# 4_Solder-Pen.net
KiCad netlist of a schematic drawn in Altium Designer
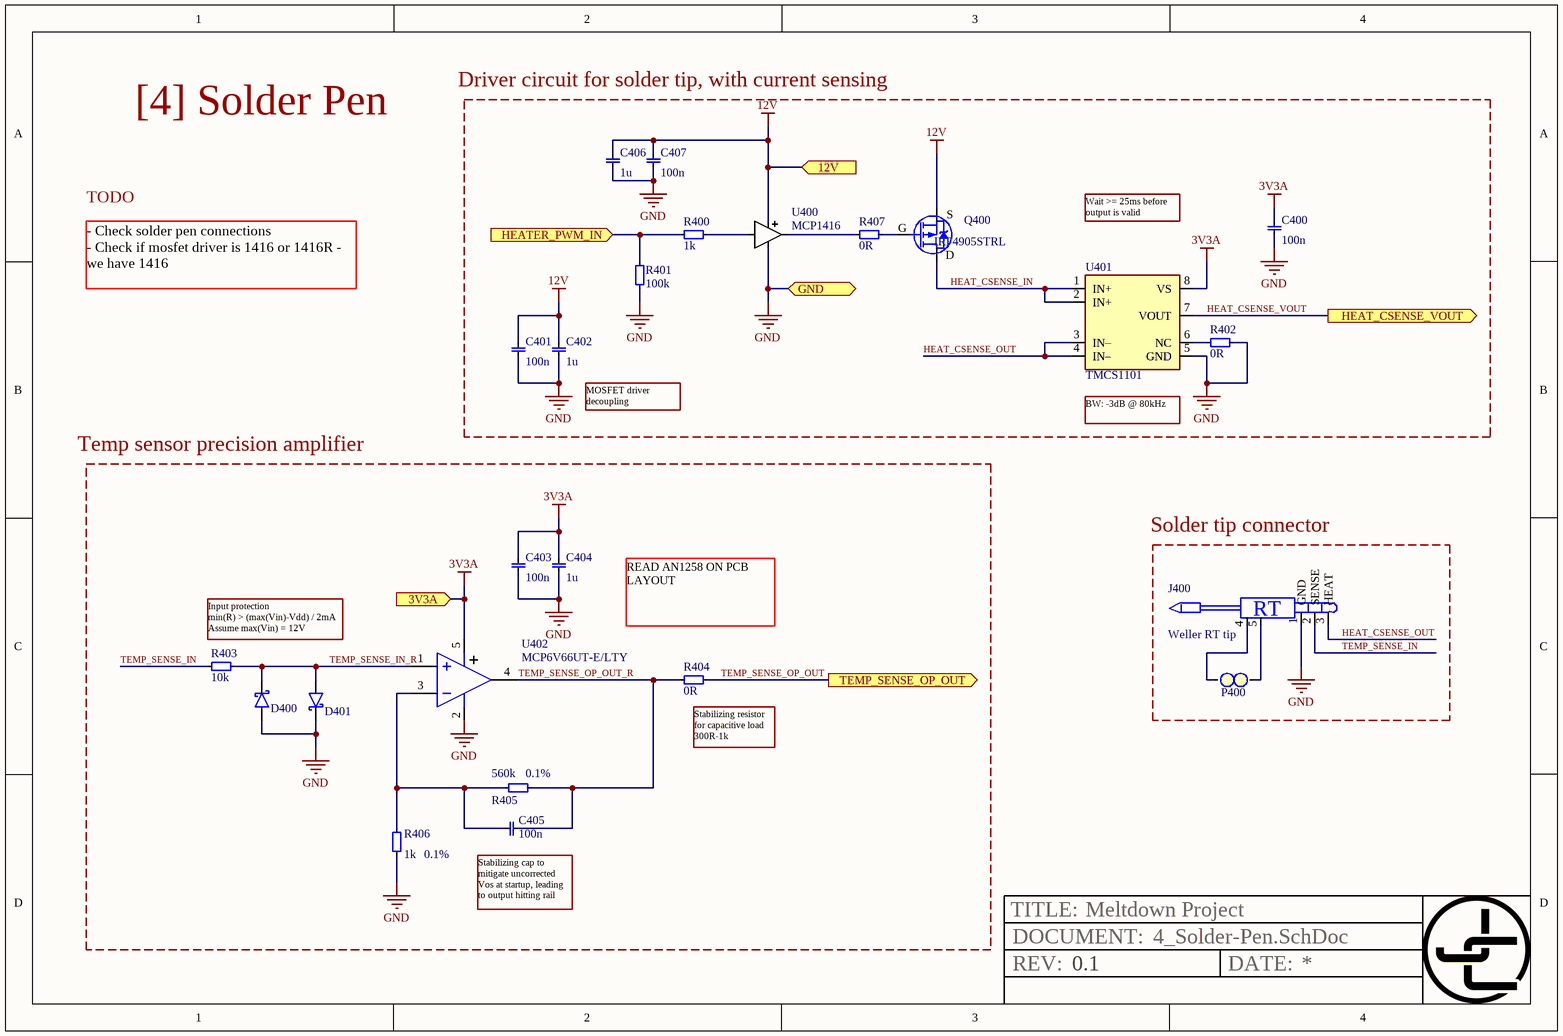
[diagram p0: 4_Solder-Pen.SchDoc]

(export (version "E")
  (design (tool "Eeschema 10.0.6"))
  (components
    (comp (ref "C400")
      (value "100n")
      (footprint "0805, cap")
      (fields (field (name "Comment") "0805, capacitor"))
      (libsource (lib "jclib") (part "0805, capacitor"))
    )
    (comp (ref "C401")
      (value "100n")
      (footprint "0805, cap")
      (fields (field (name "Comment") "0805, capacitor"))
      (libsource (lib "jclib") (part "0805, capacitor"))
    )
    (comp (ref "C402")
      (value "1u")
      (footprint "0805, cap")
      (fields (field (name "Comment") "0805, capacitor"))
      (libsource (lib "jclib") (part "0805, capacitor"))
    )
    (comp (ref "C403")
      (value "100n")
      (footprint "0805, cap")
      (fields (field (name "Comment") "0805, capacitor"))
      (libsource (lib "jclib") (part "0805, capacitor"))
    )
    (comp (ref "C404")
      (value "1u")
      (footprint "0805, cap")
      (fields (field (name "Comment") "0805, capacitor"))
      (libsource (lib "jclib") (part "0805, capacitor"))
    )
    (comp (ref "C405")
      (value "100n")
      (footprint "0805, cap")
      (fields (field (name "Comment") "0805, capacitor"))
      (libsource (lib "jclib") (part "0805, capacitor"))
    )
    (comp (ref "C406")
      (value "1u")
      (footprint "0805, cap")
      (fields (field (name "Comment") "0805, capacitor"))
      (libsource (lib "jclib") (part "0805, capacitor"))
    )
    (comp (ref "C407")
      (value "100n")
      (footprint "0805, cap")
      (fields (field (name "Comment") "0805, capacitor"))
      (libsource (lib "jclib") (part "0805, capacitor"))
    )
    (comp (ref "D400")
      (value "B340A")
      (footprint "DO-214AC")
      (description "SchottkydiodE, 40 V, 3 A")
      (libsource (lib "jclib") (part "B340A-E3/61T"))
    )
    (comp (ref "D401")
      (value "B340A")
      (footprint "DO-214AC")
      (description "SchottkydiodE, 40 V, 3 A")
      (libsource (lib "jclib") (part "B340A-E3/61T"))
    )
    (comp (ref "J400")
      (value "Weller RT tip")
      (footprint "5 POLE BLOCK CONNECTOR")
      (libsource (lib "jclib") (part "Weller RT tip"))
    )
    (comp (ref "P400")
      (value "1x2 Pin Heade Straight")
      (footprint "padtwo_L")
      (description "2.54 mm, TH")
      (libsource (lib "jclib") (part "1x2 Pin Heade Straight"))
    )
    (comp (ref "Q400")
      (value "IRF4905")
      (footprint "d2pak")
      (description "P-Channel HEXFET® Power MOSFET")
      (libsource (lib "jclib") (part "IRF4905"))
    )
    (comp (ref "R400")
      (value "1k")
      (footprint "0603")
      (fields (field (name "Comment") "0603, resistor"))
      (libsource (lib "jclib") (part "0603, resistor"))
    )
    (comp (ref "R401")
      (value "100k")
      (footprint "0603")
      (fields (field (name "Comment") "0603, resistor"))
      (libsource (lib "jclib") (part "0603, resistor"))
    )
    (comp (ref "R402")
      (value "0R")
      (footprint "0603")
      (fields (field (name "Comment") "0603, resistor"))
      (libsource (lib "jclib") (part "0603, resistor"))
    )
    (comp (ref "R403")
      (value "10k")
      (footprint "0603")
      (fields (field (name "Comment") "0603, resistor"))
      (libsource (lib "jclib") (part "0603, resistor"))
    )
    (comp (ref "R404")
      (value "0R")
      (footprint "0603")
      (fields (field (name "Comment") "0603, resistor"))
      (libsource (lib "jclib") (part "0603, resistor"))
    )
    (comp (ref "R405")
      (value "560k")
      (footprint "0603")
      (fields (field (name "TOLERANCE") "0.1%") (field (name "Comment") "0603, resistor"))
      (libsource (lib "jclib") (part "0603, resistor"))
    )
    (comp (ref "R406")
      (value "1k")
      (footprint "0603")
      (fields (field (name "TOLERANCE") "0.1%") (field (name "Comment") "0603, resistor"))
      (libsource (lib "jclib") (part "0603, resistor"))
    )
    (comp (ref "R407")
      (value "0R")
      (footprint "0603")
      (fields (field (name "Comment") "0603, resistor"))
      (libsource (lib "jclib") (part "0603, resistor"))
    )
    (comp (ref "U400")
      (value "MCP1416")
      (footprint "SOT23-5")
      (description "High-speed Power MOSFET driver")
      (libsource (lib "jclib") (part "MCP1416"))
    )
    (comp (ref "U401")
      (value "TMCS1101")
      (footprint "SOIC8")
      (description "Hall-Effect Current Sensor")
      (libsource (lib "jclib") (part "TMCS1101"))
    )
    (comp (ref "U402")
      (value "MCP6V66UT-E/LTY")
      (footprint "SC70P210X110-5N")
      (description "Linear High Precision Op Amps-Chopper Stabilized, 1000kHz, 1.8Vto5.5V, SC70-5, RoHS")
      (fields (field (name "MANUFACTURER") "Microchip"))
      (libsource (lib "jclib") (part "MCP6V66UT-E/LTY"))
    )
  )
  (nets
    (net (code "1") (name "/HEATER_PWM_IN") (class "Default")
      (node (ref "R400") (pin "1") (pinfunction "1_1") (pintype "passive"))
      (node (ref "R401") (pin "0") (pinfunction "0_0") (pintype "passive"))
    )
    (net (code "2") (name "/HEAT_CSENSE_IN") (class "Default")
      (node (ref "Q400") (pin "2") (pinfunction "D_2") (pintype "passive"))
      (node (ref "U401") (pin "1") (pinfunction "IN+_1") (pintype "passive"))
      (node (ref "U401") (pin "2") (pinfunction "IN+_2") (pintype "passive"))
    )
    (net (code "3") (name "/HEAT_CSENSE_OUT") (class "Default")
      (node (ref "J400") (pin "3") (pinfunction "HEAT_3") (pintype "passive"))
      (node (ref "U401") (pin "3") (pinfunction "IN–_3") (pintype "passive"))
      (node (ref "U401") (pin "4") (pinfunction "IN–_4") (pintype "passive"))
    )
    (net (code "4") (name "/HEAT_CSENSE_VOUT") (class "Default")
      (node (ref "U401") (pin "7") (pinfunction "VOUT_7") (pintype "passive"))
    )
    (net (code "5") (name "/TEMP_SENSE_IN") (class "Default")
      (node (ref "J400") (pin "2") (pinfunction "SENSE_2") (pintype "passive"))
      (node (ref "R403") (pin "0") (pinfunction "0_0") (pintype "passive"))
    )
    (net (code "6") (name "/TEMP_SENSE_IN_R") (class "Default")
      (node (ref "D400") (pin "1") (pinfunction "K_1") (pintype "passive"))
      (node (ref "D401") (pin "2") (pinfunction "A_2") (pintype "passive"))
      (node (ref "R403") (pin "1") (pinfunction "1_1") (pintype "passive"))
      (node (ref "U402") (pin "1") (pinfunction "IN+_1") (pintype "passive"))
    )
    (net (code "7") (name "/TEMP_SENSE_OP_OUT") (class "Default")
      (node (ref "R404") (pin "1") (pinfunction "1_1") (pintype "passive"))
    )
    (net (code "8") (name "/TEMP_SENSE_OP_OUT_R") (class "Default")
      (node (ref "C405") (pin "0") (pinfunction "0_0") (pintype "passive"))
      (node (ref "R404") (pin "0") (pinfunction "0_0") (pintype "passive"))
      (node (ref "R405") (pin "1") (pinfunction "1_1") (pintype "passive"))
      (node (ref "U402") (pin "4") (pinfunction "OUT_4") (pintype "passive"))
    )
    (net (code "9") (name "3V3A") (class "Default")
      (node (ref "C400") (pin "1") (pinfunction "1_1") (pintype "passive"))
      (node (ref "C403") (pin "1") (pinfunction "1_1") (pintype "passive"))
      (node (ref "C404") (pin "1") (pinfunction "1_1") (pintype "passive"))
      (node (ref "U401") (pin "8") (pinfunction "VS_8") (pintype "passive"))
      (node (ref "U402") (pin "5") (pinfunction "V+_5") (pintype "passive"))
    )
    (net (code "10") (name "12V") (class "Default")
      (node (ref "C401") (pin "1") (pinfunction "1_1") (pintype "passive"))
      (node (ref "C402") (pin "1") (pinfunction "1_1") (pintype "passive"))
      (node (ref "C406") (pin "1") (pinfunction "1_1") (pintype "passive"))
      (node (ref "C407") (pin "1") (pinfunction "1_1") (pintype "passive"))
      (node (ref "Q400") (pin "3") (pinfunction "S_3") (pintype "passive"))
      (node (ref "U400") (pin "5") (pinfunction "5_5") (pintype "passive"))
    )
    (net (code "11") (name "GND") (class "Default")
      (node (ref "C400") (pin "0") (pinfunction "0_0") (pintype "passive"))
      (node (ref "C401") (pin "0") (pinfunction "0_0") (pintype "passive"))
      (node (ref "C402") (pin "0") (pinfunction "0_0") (pintype "passive"))
      (node (ref "C403") (pin "0") (pinfunction "0_0") (pintype "passive"))
      (node (ref "C404") (pin "0") (pinfunction "0_0") (pintype "passive"))
      (node (ref "C406") (pin "0") (pinfunction "0_0") (pintype "passive"))
      (node (ref "C407") (pin "0") (pinfunction "0_0") (pintype "passive"))
      (node (ref "D400") (pin "2") (pinfunction "A_2") (pintype "passive"))
      (node (ref "D401") (pin "1") (pinfunction "K_1") (pintype "passive"))
      (node (ref "J400") (pin "1") (pinfunction "GND_1") (pintype "passive"))
      (node (ref "R401") (pin "1") (pinfunction "1_1") (pintype "passive"))
      (node (ref "R402") (pin "1") (pinfunction "1_1") (pintype "passive"))
      (node (ref "R406") (pin "1") (pinfunction "1_1") (pintype "passive"))
      (node (ref "U400") (pin "2") (pinfunction "2_2") (pintype "passive"))
      (node (ref "U401") (pin "5") (pinfunction "GND_5") (pintype "passive"))
      (node (ref "U402") (pin "2") (pinfunction "V-_2") (pintype "passive"))
    )
    (net (code "12") (name "Net-(J400-Pad4)") (class "Default")
      (node (ref "J400") (pin "4") (pinfunction "4_4") (pintype "passive"))
      (node (ref "P400") (pin "1") (pinfunction "1_1") (pintype "passive"))
    )
    (net (code "13") (name "Net-(J400-Pad5)") (class "Default")
      (node (ref "J400") (pin "5") (pinfunction "5_5") (pintype "passive"))
      (node (ref "P400") (pin "2") (pinfunction "2_2") (pintype "passive"))
    )
    (net (code "14") (name "Net-(Q400-G)") (class "Default")
      (node (ref "Q400") (pin "1") (pinfunction "G_1") (pintype "passive"))
      (node (ref "R407") (pin "0") (pinfunction "0_0") (pintype "passive"))
    )
    (net (code "15") (name "Net-(R400-Pad0)") (class "Default")
      (node (ref "R400") (pin "0") (pinfunction "0_0") (pintype "passive"))
      (node (ref "U400") (pin "3") (pinfunction "3_3") (pintype "passive"))
    )
    (net (code "16") (name "Net-(R407-Pad1)") (class "Default")
      (node (ref "R407") (pin "1") (pinfunction "1_1") (pintype "passive"))
      (node (ref "U400") (pin "4") (pinfunction "4_4") (pintype "passive"))
    )
    (net (code "17") (name "Net-(U401-NC)") (class "Default")
      (node (ref "R402") (pin "0") (pinfunction "0_0") (pintype "passive"))
      (node (ref "U401") (pin "6") (pinfunction "NC_6") (pintype "passive"))
    )
    (net (code "18") (name "Net-(U402-IN-)") (class "Default")
      (node (ref "C405") (pin "1") (pinfunction "1_1") (pintype "passive"))
      (node (ref "R405") (pin "0") (pinfunction "0_0") (pintype "passive"))
      (node (ref "R406") (pin "0") (pinfunction "0_0") (pintype "passive"))
      (node (ref "U402") (pin "3") (pinfunction "IN-_3") (pintype "passive"))
    )
  )
)
